# Optical_RX_TX.net
KiCad netlist of a schematic drawn in Altium Designer
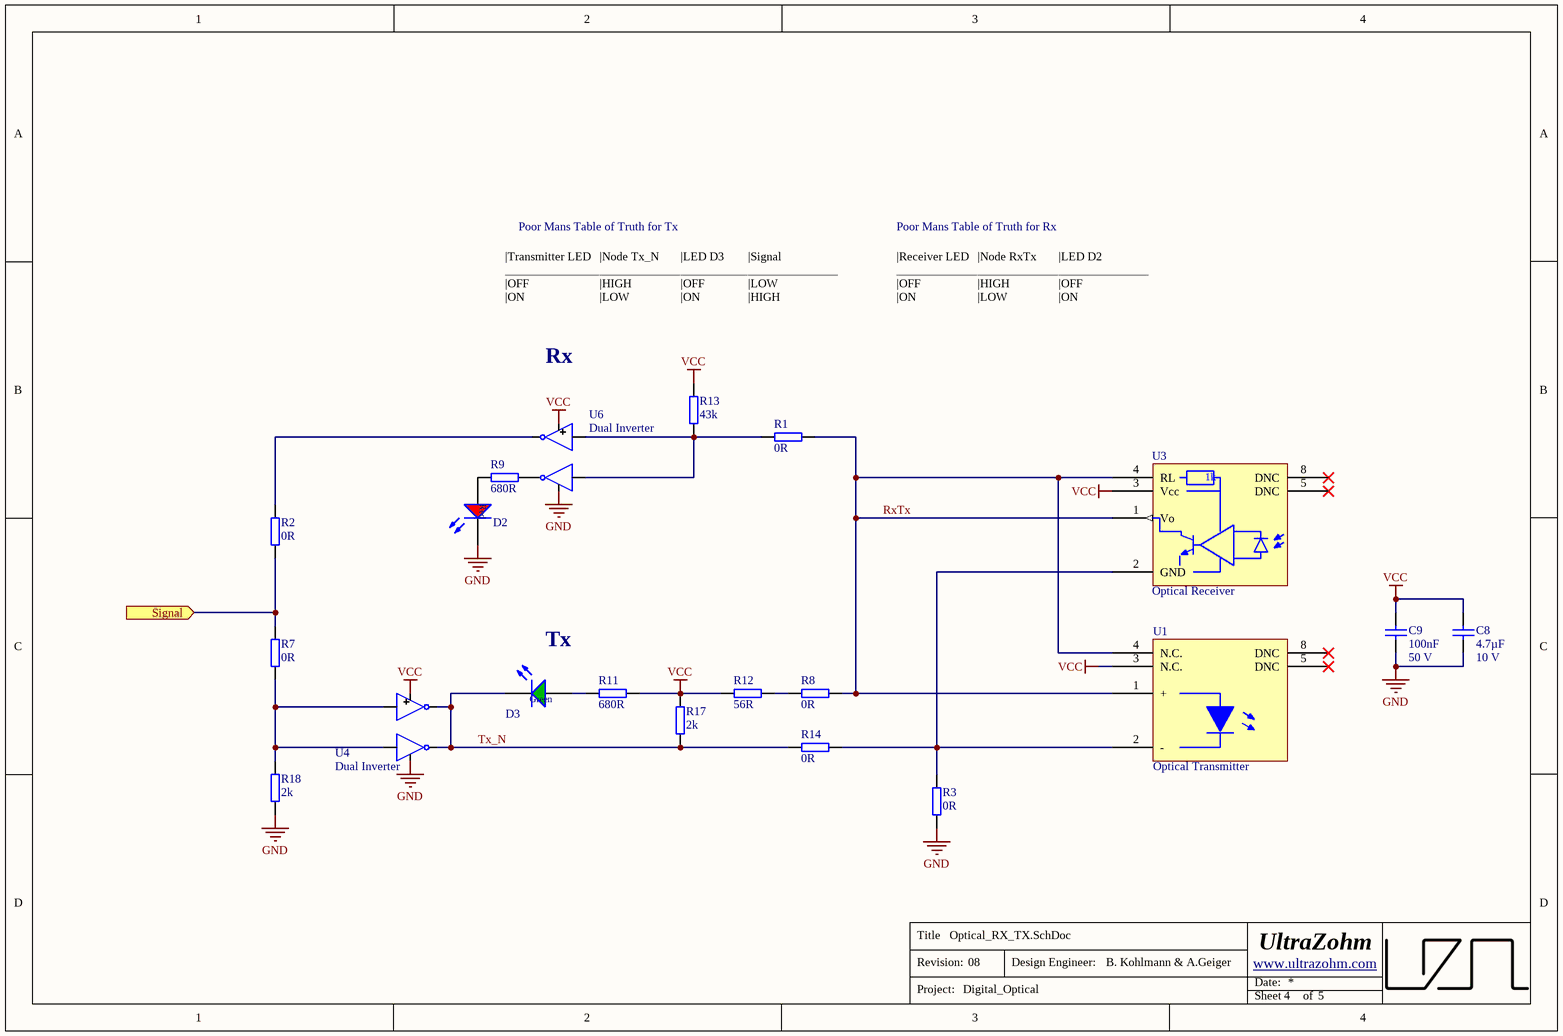
[diagram p0: Optical_RX_TX.SchDoc]

(export (version "E")
  (design (tool "Eeschema 10.0.6"))
  (components
    (comp (ref "C8")
      (value "4.7µF")
      (footprint "CAP_2012X06N")
      (description "CAP 0805 (2012 Metric) SMD")
      (fields
        (field (name "TOLERANCE") "±10%")
        (field (name "MF") "Taiyo Yuden")
        (field (name "VOLTAGE") "10 V")
        (field (name "CREATED") "2018_09_06_AGeiger")
      )
      (libsource (lib "UZOhm_Optical") (part "C_0805"))
    )
    (comp (ref "C9")
      (value "100nF")
      (footprint "C_0603(1608)100_L")
      (description "CAP 0603 (1608 Metric) SMD")
      (fields
        (field (name "TOLERANCE") "±5%")
        (field (name "LCSC PART #") "C14663")
        (field (name "RATED VOLTAGE") "50 V")
        (field (name "CREATED") "2018_09_06_AGeiger")
      )
      (libsource (lib "UZOhm_Optical") (part "C_0603"))
    )
    (comp (ref "D2")
      (value "150060RS75000")
      (footprint "WL-SMCW_0603")
      (description "WL-SMCW SMD Mono-color Chip LED Waterclear, size 0603, Red, 2 V, 140°")
      (fields
        (field (name "MF") "Wuerth Elektronik")
        (field (name "LCSC PART #") "C2286")
        (field (name "CREATED") "2018_09_06_AGeiger")
      )
      (libsource (lib "UZOhm_Optical") (part "LED_Red_0603"))
    )
    (comp (ref "D3")
      (value "150060GS75000")
      (footprint "WL-SMCW_0603")
      (description "WL-SMCW SMD Mono-color Chip LED Waterclear, size 0603, Green, 3.2 V, 140°")
      (fields
        (field (name "MF") "Wuerth Elektronik")
        (field (name "LCSC PART #") "C965804")
        (field (name "CREATED") "2018_09_06_AGeiger")
      )
      (libsource (lib "UZOhm_Optical") (part "LED_Green_0603"))
    )
    (comp (ref "R1")
      (value "0R")
      (footprint "R_0603_N")
      (description "SMD Resistor 0603")
      (fields
        (field (name "TOLERANCE") "1%")
        (field (name "VOLTAGE") "75V")
        (field (name "CREATED") "2018_09_06_AGeiger")
      )
      (libsource (lib "UZOhm_Optical") (part "R_0603_JLC"))
    )
    (comp (ref "R2")
      (value "0R")
      (footprint "R_0603_N")
      (description "SMD Resistor 0603")
      (fields
        (field (name "TOLERANCE") "1%")
        (field (name "VOLTAGE") "75V")
        (field (name "CREATED") "2018_09_06_AGeiger")
      )
      (libsource (lib "UZOhm_Optical") (part "R_0603_JLC"))
    )
    (comp (ref "R3")
      (value "0R")
      (footprint "R_0603_N")
      (description "SMD Resistor 0603")
      (fields
        (field (name "TOLERANCE") "1%")
        (field (name "VOLTAGE") "75V")
        (field (name "CREATED") "2018_09_06_AGeiger")
      )
      (libsource (lib "UZOhm_Optical") (part "R_0603"))
    )
    (comp (ref "R7")
      (value "0R")
      (footprint "R_0603_N")
      (description "SMD Resistor 0603")
      (fields
        (field (name "TOLERANCE") "1%")
        (field (name "VOLTAGE") "75V")
        (field (name "CREATED") "2018_09_06_AGeiger")
      )
      (libsource (lib "UZOhm_Optical") (part "R_0603_JLC"))
    )
    (comp (ref "R8")
      (value "0R")
      (footprint "R_0603_N")
      (description "SMD Resistor 0603")
      (fields
        (field (name "TOLERANCE") "1%")
        (field (name "VOLTAGE") "75V")
        (field (name "CREATED") "2018_09_06_AGeiger")
      )
      (libsource (lib "UZOhm_Optical") (part "R_0603_JLC"))
    )
    (comp (ref "R9")
      (value "680R")
      (footprint "R_0603_N")
      (description "SMD Resistor 0603")
      (fields
        (field (name "TOLERANCE") "1%")
        (field (name "VOLTAGE") "75V")
        (field (name "CREATED") "2018_09_06_AGeiger")
      )
      (libsource (lib "UZOhm_Optical") (part "R_0603"))
    )
    (comp (ref "R11")
      (value "680R")
      (footprint "R_0603_N")
      (description "SMD Resistor 0603")
      (fields
        (field (name "TOLERANCE") "1%")
        (field (name "VOLTAGE") "75V")
        (field (name "CREATED") "2018_09_06_AGeiger")
      )
      (libsource (lib "UZOhm_Optical") (part "R_0603"))
    )
    (comp (ref "R12")
      (value "56R")
      (footprint "RES_2012X06N")
      (description "SMD Resistor 0805")
      (fields (field (name "MF") "Bourns") (field (name "MPN") "CR0805-FX-1200ELF"))
      (libsource (lib "UZOhm_Optical") (part "R_0805"))
    )
    (comp (ref "R13")
      (value "43k")
      (footprint "R_0603_N")
      (description "SMD Resistor 0603")
      (fields
        (field (name "TOLERANCE") "1%")
        (field (name "VOLTAGE") "50V")
        (field (name "CREATED") "2018_09_06_AGeiger")
      )
      (libsource (lib "UZOhm_Optical") (part "R_0603_JLC"))
    )
    (comp (ref "R14")
      (value "0R")
      (footprint "R_0603_N")
      (description "SMD Resistor 0603")
      (fields
        (field (name "TOLERANCE") "1%")
        (field (name "VOLTAGE") "75V")
        (field (name "CREATED") "2018_09_06_AGeiger")
      )
      (libsource (lib "UZOhm_Optical") (part "R_0603_JLC"))
    )
    (comp (ref "R17")
      (value "2k")
      (footprint "R_0603_N")
      (description "SMD Resistor 0603")
      (fields
        (field (name "TOLERANCE") "1%")
        (field (name "VOLTAGE") "75 V")
        (field (name "CREATED") "2018_09_06_AGeiger")
      )
      (libsource (lib "UZOhm_Optical") (part "R_0603"))
    )
    (comp (ref "R18")
      (value "2k")
      (footprint "R_0603_N")
      (description "SMD Resistor 0603")
      (fields
        (field (name "TOLERANCE") "1%")
        (field (name "VOLTAGE") "75 V")
        (field (name "CREATED") "2018_09_06_AGeiger")
      )
      (libsource (lib "UZOhm_Optical") (part "R_0603"))
    )
    (comp (ref "U1")
      (value "Optical Transmitter")
      (footprint "HFBRx5XX")
      (description "Fibre Optic Transmitters, Link Horiz 5MBd Tx RoHS")
      (fields
        (field (name "MF") "Broadcom/Avago")
        (field (name "MPN") "HFBR-1521Z")
        (field (name "CREATED") "2019_04_09_Kreppel")
      )
      (libsource (lib "UZOhm_Optical") (part "HFBR-1521Z"))
    )
    (comp (ref "U3")
      (value "Optical Receiver")
      (footprint "HFBRx5XX")
      (description "Fibre Optic Receivers, LINK HORIZ 5MBd RC VR RoHS")
      (fields
        (field (name "MF") "Boadcom/Avago")
        (field (name "MPN") "HFBR-2521Z")
        (field (name "CREATED") "2019_04_09_Kreppel")
      )
      (libsource (lib "UZOhm_Optical") (part "HFBR-2528Z"))
    )
    (comp (ref "U4")
      (value "Dual Inverter")
      (footprint "SN74LVC2GU04DCKR")
      (description "This dual inverter is designed for 1.65-V to 5.5-V VCC\r\noperation.")
      (fields (field (name "LCSC PART #") "C116660"))
      (libsource (lib "UZOhm_Optical") (part "SN74LVC2GU04DCKR"))
    )
    (comp (ref "U6")
      (value "Dual Inverter")
      (footprint "SN74LVC2GU04DCKR")
      (description "This dual inverter is designed for 1.65-V to 5.5-V VCC\r\noperation.")
      (fields (field (name "LCSC PART #") "C116660"))
      (libsource (lib "UZOhm_Optical") (part "SN74LVC2GU04DCKR"))
    )
  )
  (nets
    (net (code "1") (name "/RxTx") (class "Default")
      (node (ref "R1") (pin "2") (pinfunction "2_2") (pintype "passive"))
      (node (ref "R8") (pin "2") (pinfunction "2_2") (pintype "passive"))
      (node (ref "U1") (pin "1") (pinfunction "+_1") (pintype "passive"))
      (node (ref "U1") (pin "4") (pinfunction "N.C._4") (pintype "passive"))
      (node (ref "U3") (pin "1") (pinfunction "Vo_1") (pintype "output"))
      (node (ref "U3") (pin "4") (pinfunction "RL_4") (pintype "passive"))
    )
    (net (code "2") (name "/Signal") (class "Default")
      (node (ref "R2") (pin "1") (pinfunction "1_1") (pintype "passive"))
      (node (ref "R7") (pin "2") (pinfunction "2_2") (pintype "passive"))
    )
    (net (code "3") (name "/Tx_N") (class "Default")
      (node (ref "D3") (pin "1") (pinfunction "K_1") (pintype "passive"))
      (node (ref "R14") (pin "1") (pinfunction "1_1") (pintype "passive"))
      (node (ref "R17") (pin "1") (pinfunction "1_1") (pintype "passive"))
      (node (ref "U4") (pin "4") (pinfunction "OUT2_4") (pintype "passive"))
      (node (ref "U4") (pin "6") (pinfunction "OUT2_6") (pintype "passive"))
    )
    (net (code "4") (name "GND") (class "Default")
      (node (ref "C8") (pin "2") (pinfunction "2_2") (pintype "passive"))
      (node (ref "C9") (pin "2") (pinfunction "2_2") (pintype "passive"))
      (node (ref "D2") (pin "1") (pinfunction "K_1") (pintype "passive"))
      (node (ref "R18") (pin "1") (pinfunction "1_1") (pintype "passive"))
      (node (ref "R3") (pin "2") (pinfunction "2_2") (pintype "passive"))
      (node (ref "U4") (pin "2") (pinfunction "GND_2") (pintype "passive"))
      (node (ref "U6") (pin "2") (pinfunction "GND_2") (pintype "passive"))
    )
    (net (code "5") (name "Net-(D2-A)") (class "Default")
      (node (ref "D2") (pin "2") (pinfunction "A_2") (pintype "passive"))
      (node (ref "R9") (pin "2") (pinfunction "2_2") (pintype "passive"))
    )
    (net (code "6") (name "Net-(D3-A)") (class "Default")
      (node (ref "D3") (pin "2") (pinfunction "A_2") (pintype "passive"))
      (node (ref "R11") (pin "2") (pinfunction "2_2") (pintype "passive"))
    )
    (net (code "7") (name "Net-(R2-Pad2)") (class "Default")
      (node (ref "R2") (pin "2") (pinfunction "2_2") (pintype "passive"))
      (node (ref "U6") (pin "6") (pinfunction "OUT2_6") (pintype "passive"))
    )
    (net (code "8") (name "Net-(R9-Pad1)") (class "Default")
      (node (ref "R9") (pin "1") (pinfunction "1_1") (pintype "passive"))
      (node (ref "U6") (pin "4") (pinfunction "OUT2_4") (pintype "passive"))
    )
    (net (code "9") (name "Net-(R12-Pad2)") (class "Default")
      (node (ref "R12") (pin "2") (pintype "passive"))
      (node (ref "R8") (pin "1") (pinfunction "1_1") (pintype "passive"))
    )
    (net (code "10") (name "Net-(U1--)") (class "Default")
      (node (ref "R14") (pin "2") (pinfunction "2_2") (pintype "passive"))
      (node (ref "R3") (pin "1") (pinfunction "1_1") (pintype "passive"))
      (node (ref "U1") (pin "2") (pinfunction "-_2") (pintype "passive"))
      (node (ref "U3") (pin "2") (pinfunction "GND_2") (pintype "power_in"))
    )
    (net (code "11") (name "Net-(U4-IN1)") (class "Default")
      (node (ref "R18") (pin "2") (pinfunction "2_2") (pintype "passive"))
      (node (ref "R7") (pin "1") (pinfunction "1_1") (pintype "passive"))
      (node (ref "U4") (pin "1") (pinfunction "IN1_1") (pintype "passive"))
      (node (ref "U4") (pin "3") (pinfunction "IN2_3") (pintype "passive"))
    )
    (net (code "12") (name "Net-(U6-IN1)") (class "Default")
      (node (ref "R1") (pin "1") (pinfunction "1_1") (pintype "passive"))
      (node (ref "R13") (pin "2") (pinfunction "2_2") (pintype "passive"))
      (node (ref "U6") (pin "1") (pinfunction "IN1_1") (pintype "passive"))
      (node (ref "U6") (pin "3") (pinfunction "IN2_3") (pintype "passive"))
    )
    (net (code "13") (name "VCC") (class "Default")
      (node (ref "C8") (pin "1") (pinfunction "1_1") (pintype "passive"))
      (node (ref "C9") (pin "1") (pinfunction "1_1") (pintype "passive"))
      (node (ref "R11") (pin "1") (pinfunction "1_1") (pintype "passive"))
      (node (ref "R12") (pin "1") (pintype "passive"))
      (node (ref "R13") (pin "1") (pinfunction "1_1") (pintype "passive"))
      (node (ref "R17") (pin "2") (pinfunction "2_2") (pintype "passive"))
      (node (ref "U1") (pin "3") (pinfunction "N.C._3") (pintype "passive"))
      (node (ref "U3") (pin "3") (pinfunction "Vcc_3") (pintype "power_in"))
      (node (ref "U4") (pin "5") (pinfunction "VCC_5") (pintype "passive"))
      (node (ref "U6") (pin "5") (pinfunction "VCC_5") (pintype "passive"))
    )
    (net (code "14") (name "unconnected-(U1-DNC-Pad5)") (class "Default")
      (node (ref "U1") (pin "5") (pinfunction "DNC_5") (pintype "passive+no_connect"))
    )
    (net (code "15") (name "unconnected-(U1-DNC-Pad8)") (class "Default")
      (node (ref "U1") (pin "8") (pinfunction "DNC_8") (pintype "passive+no_connect"))
    )
    (net (code "16") (name "unconnected-(U3-DNC-Pad5)") (class "Default")
      (node (ref "U3") (pin "5") (pinfunction "DNC_5") (pintype "passive+no_connect"))
    )
    (net (code "17") (name "unconnected-(U3-DNC-Pad8)") (class "Default")
      (node (ref "U3") (pin "8") (pinfunction "DNC_8") (pintype "passive+no_connect"))
    )
  )
)
